# design.net
KiCad netlist of a schematic drawn in EasyEDA
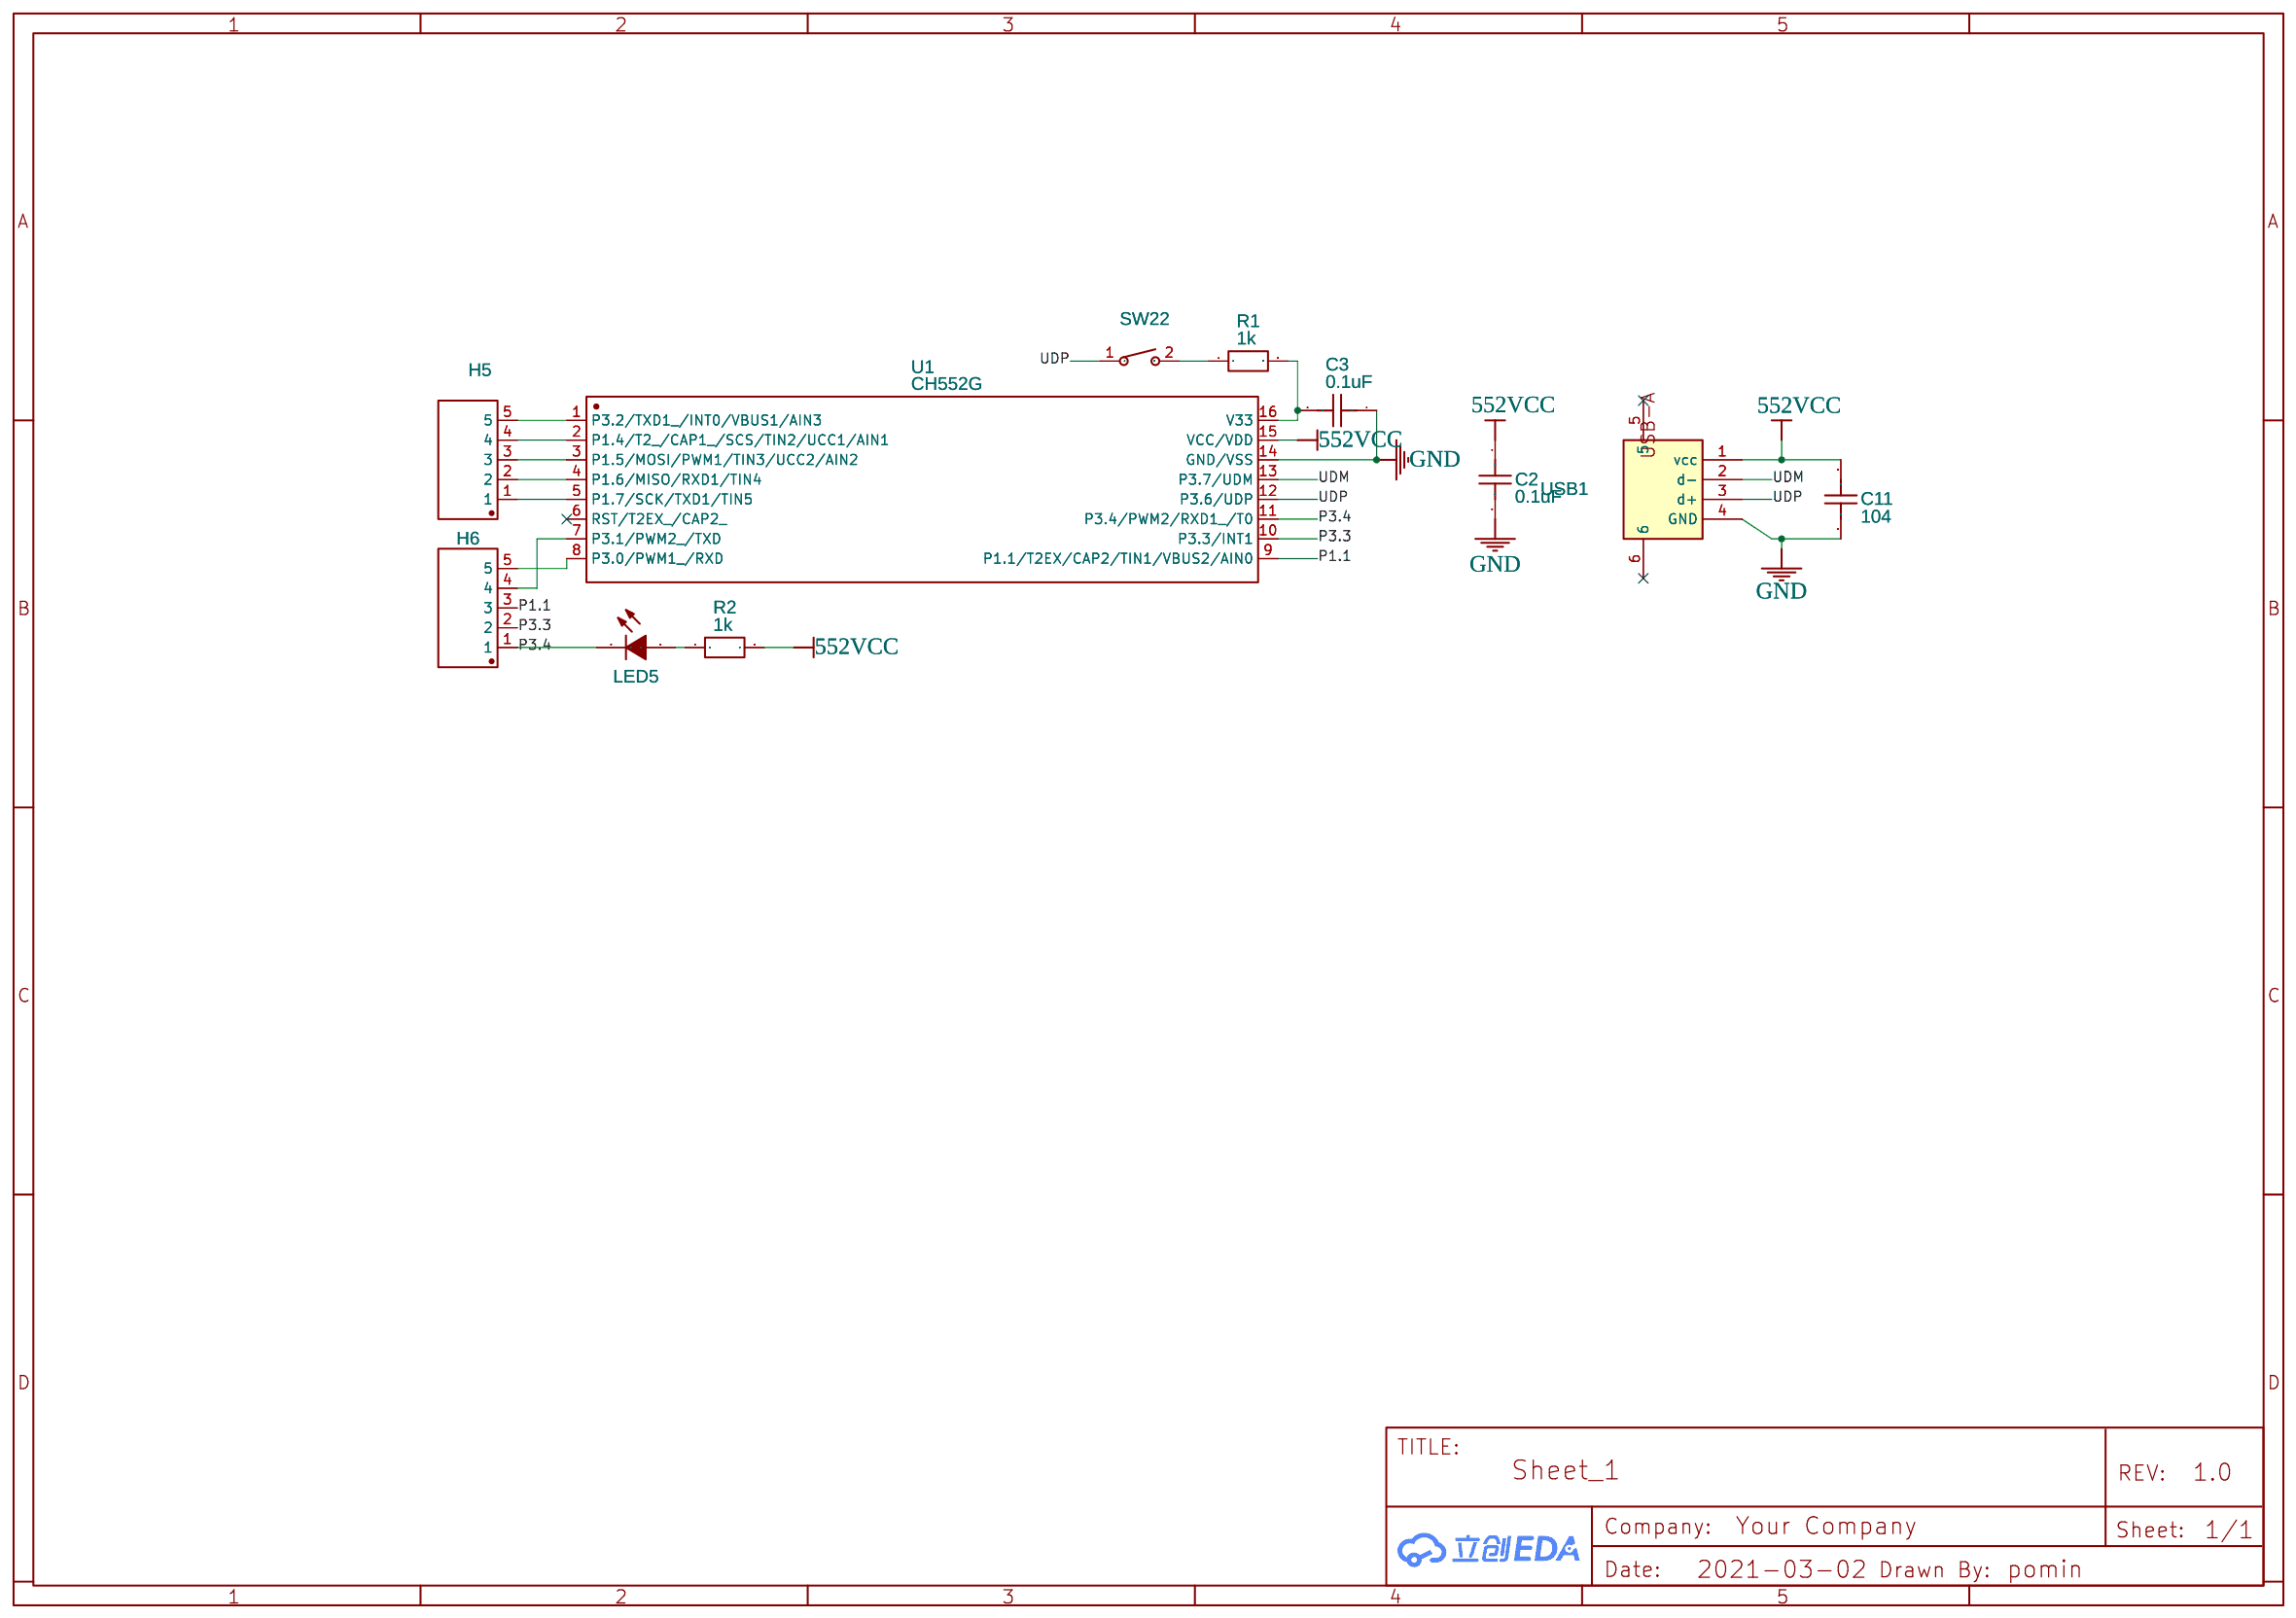
[diagram p0: schematic sheet]

(export (version "E")
  (design (tool "Eeschema 10.0.6"))
  (components
    (comp (ref "C2") (value "0.1uF") (libsource (lib "") (part "C_0201_US_1")))
    (comp (ref "C3") (value "0.1uF") (libsource (lib "") (part "C_0201_US")))
    (comp (ref "C11") (value "104") (libsource (lib "") (part "C_0805_US")))
    (comp (ref "H5")
      (value "210S-1*5P L=11.6MMGold-plated black")
      (fields (field (name "BOM_Supplier Part") "C124379"))
      (libsource (lib "") (part "210S-1*5P L=11.6MMGold-plated black"))
    )
    (comp (ref "H6")
      (value "210S-1*5P L=11.6MMGold-plated black")
      (fields (field (name "BOM_Supplier Part") "C124379"))
      (libsource (lib "") (part "210S-1*5P L=11.6MMGold-plated black"))
    )
    (comp (ref "LED5")
      (value "17-21SURC/S530-A3/TR8")
      (fields (field (name "BOM_Supplier Part") "C72037"))
      (libsource (lib "") (part "17-21SURC/S530-A3/TR8"))
    )
    (comp (ref "R1") (value "1k") (libsource (lib "") (part "R_0201_EU")))
    (comp (ref "R2") (value "1k") (libsource (lib "") (part "R_0201_EU")))
    (comp (ref "SW22")
      (value "UK-B0227-G4.3-160-W-JZ")
      (fields (field (name "BOM_Supplier Part") "C620345"))
      (libsource (lib "") (part "UK-B0227-G4.3-160-W-JZ"))
    )
    (comp (ref "U1")
      (value "CH552G")
      (fields (field (name "BOM_Supplier Part") "C111292"))
      (libsource (lib "") (part "CH552G"))
    )
    (comp (ref "USB1")
      (value "U-G-04WS-W-01")
      (fields (field (name "BOM_Supplier Part") "C97324"))
      (libsource (lib "") (part "U-G-04WS-W-01"))
    )
  )
  (nets
    (net (code "1") (name "/P1.1") (class "Default")
      (node (ref "H6") (pin "3") (pinfunction "3_3") (pintype "unspecified"))
      (node (ref "U1") (pin "9") (pinfunction "P1.1/T2EX/CAP2/TIN1/VBUS2/AIN0_9") (pintype "unspecified"))
    )
    (net (code "2") (name "/P3.3") (class "Default")
      (node (ref "H6") (pin "2") (pinfunction "2_2") (pintype "unspecified"))
      (node (ref "U1") (pin "10") (pinfunction "P3.3/INT1_10") (pintype "unspecified"))
    )
    (net (code "3") (name "/P3.4") (class "Default")
      (node (ref "H6") (pin "1") (pinfunction "1_1") (pintype "unspecified"))
      (node (ref "LED5") (pin "2") (pinfunction "C_2") (pintype "input"))
      (node (ref "U1") (pin "11") (pinfunction "P3.4/PWM2/RXD1_/T0_11") (pintype "unspecified"))
    )
    (net (code "4") (name "/UDM") (class "Default")
      (node (ref "U1") (pin "13") (pinfunction "P3.7/UDM_13") (pintype "unspecified"))
      (node (ref "USB1") (pin "2") (pinfunction "d-_2") (pintype "unspecified"))
    )
    (net (code "5") (name "/UDP") (class "Default")
      (node (ref "SW22") (pin "1") (pinfunction "1_1") (pintype "unspecified"))
      (node (ref "U1") (pin "12") (pinfunction "P3.6/UDP_12") (pintype "unspecified"))
      (node (ref "USB1") (pin "3") (pinfunction "d+_3") (pintype "unspecified"))
    )
    (net (code "6") (name "552VCC") (class "Default")
      (node (ref "C11") (pin "2") (pinfunction "2_2") (pintype "unspecified"))
      (node (ref "C2") (pin "1") (pinfunction "1_1") (pintype "unspecified"))
      (node (ref "R2") (pin "2") (pinfunction "2_2") (pintype "unspecified"))
      (node (ref "U1") (pin "15") (pinfunction "VCC/VDD_15") (pintype "unspecified"))
      (node (ref "USB1") (pin "1") (pinfunction "vcc_1") (pintype "unspecified"))
    )
    (net (code "7") (name "GND") (class "Default")
      (node (ref "C11") (pin "1") (pinfunction "1_1") (pintype "unspecified"))
      (node (ref "C2") (pin "2") (pinfunction "2_2") (pintype "unspecified"))
      (node (ref "C3") (pin "1") (pinfunction "1_1") (pintype "unspecified"))
      (node (ref "U1") (pin "14") (pinfunction "GND/VSS_14") (pintype "unspecified"))
      (node (ref "USB1") (pin "4") (pinfunction "GND_4") (pintype "unspecified"))
    )
    (net (code "8") (name "Net-(LED5-A)") (class "Default")
      (node (ref "LED5") (pin "1") (pinfunction "A_1") (pintype "input"))
      (node (ref "R2") (pin "1") (pinfunction "1_1") (pintype "unspecified"))
    )
    (net (code "9") (name "Net-(R1-Pad1)") (class "Default")
      (node (ref "R1") (pin "1") (pinfunction "1_1") (pintype "unspecified"))
      (node (ref "SW22") (pin "2") (pinfunction "2_2") (pintype "unspecified"))
    )
    (net (code "10") (name "Net-(U1-P1.4{slash}T2_{slash}CAP1_{slash}SCS{slash}TIN2{slash}UCC1{slash}AIN1)") (class "Default")
      (node (ref "H5") (pin "4") (pinfunction "4_4") (pintype "unspecified"))
      (node (ref "U1") (pin "2") (pinfunction "P1.4/T2_/CAP1_/SCS/TIN2/UCC1/AIN1_2") (pintype "unspecified"))
    )
    (net (code "11") (name "Net-(U1-P1.5{slash}MOSI{slash}PWM1{slash}TIN3{slash}UCC2{slash}AIN2)") (class "Default")
      (node (ref "H5") (pin "3") (pinfunction "3_3") (pintype "unspecified"))
      (node (ref "U1") (pin "3") (pinfunction "P1.5/MOSI/PWM1/TIN3/UCC2/AIN2_3") (pintype "unspecified"))
    )
    (net (code "12") (name "Net-(U1-P1.6{slash}MISO{slash}RXD1{slash}TIN4)") (class "Default")
      (node (ref "H5") (pin "2") (pinfunction "2_2") (pintype "unspecified"))
      (node (ref "U1") (pin "4") (pinfunction "P1.6/MISO/RXD1/TIN4_4") (pintype "unspecified"))
    )
    (net (code "13") (name "Net-(U1-P1.7{slash}SCK{slash}TXD1{slash}TIN5)") (class "Default")
      (node (ref "H5") (pin "1") (pinfunction "1_1") (pintype "unspecified"))
      (node (ref "U1") (pin "5") (pinfunction "P1.7/SCK/TXD1/TIN5_5") (pintype "unspecified"))
    )
    (net (code "14") (name "Net-(U1-P3.0{slash}PWM1_{slash}RXD)") (class "Default")
      (node (ref "H6") (pin "5") (pinfunction "5_5") (pintype "unspecified"))
      (node (ref "U1") (pin "8") (pinfunction "P3.0/PWM1_/RXD_8") (pintype "unspecified"))
    )
    (net (code "15") (name "Net-(U1-P3.1{slash}PWM2_{slash}TXD)") (class "Default")
      (node (ref "H6") (pin "4") (pinfunction "4_4") (pintype "unspecified"))
      (node (ref "U1") (pin "7") (pinfunction "P3.1/PWM2_/TXD_7") (pintype "unspecified"))
    )
    (net (code "16") (name "Net-(U1-P3.2{slash}TXD1_{slash}INT0{slash}VBUS1{slash}AIN3)") (class "Default")
      (node (ref "H5") (pin "5") (pinfunction "5_5") (pintype "unspecified"))
      (node (ref "U1") (pin "1") (pinfunction "P3.2/TXD1_/INT0/VBUS1/AIN3_1") (pintype "unspecified"))
    )
    (net (code "17") (name "Net-(U1-V33)") (class "Default")
      (node (ref "C3") (pin "2") (pinfunction "2_2") (pintype "unspecified"))
      (node (ref "R1") (pin "2") (pinfunction "2_2") (pintype "unspecified"))
      (node (ref "U1") (pin "16") (pinfunction "V33_16") (pintype "unspecified"))
    )
    (net (code "18") (name "unconnected-(U1-RST{slash}T2EX_{slash}CAP2_-Pad6)") (class "Default")
      (node (ref "U1") (pin "6") (pinfunction "RST/T2EX_/CAP2__6") (pintype "unspecified+no_connect"))
    )
    (net (code "19") (name "unconnected-(USB1-Pad5)") (class "Default")
      (node (ref "USB1") (pin "5") (pinfunction "5_5") (pintype "unspecified+no_connect"))
    )
    (net (code "20") (name "unconnected-(USB1-Pad6)") (class "Default")
      (node (ref "USB1") (pin "6") (pinfunction "6_6") (pintype "unspecified+no_connect"))
    )
  )
)
